# SensWear_Touch.net
KiCad netlist of a schematic drawn in Altium Designer
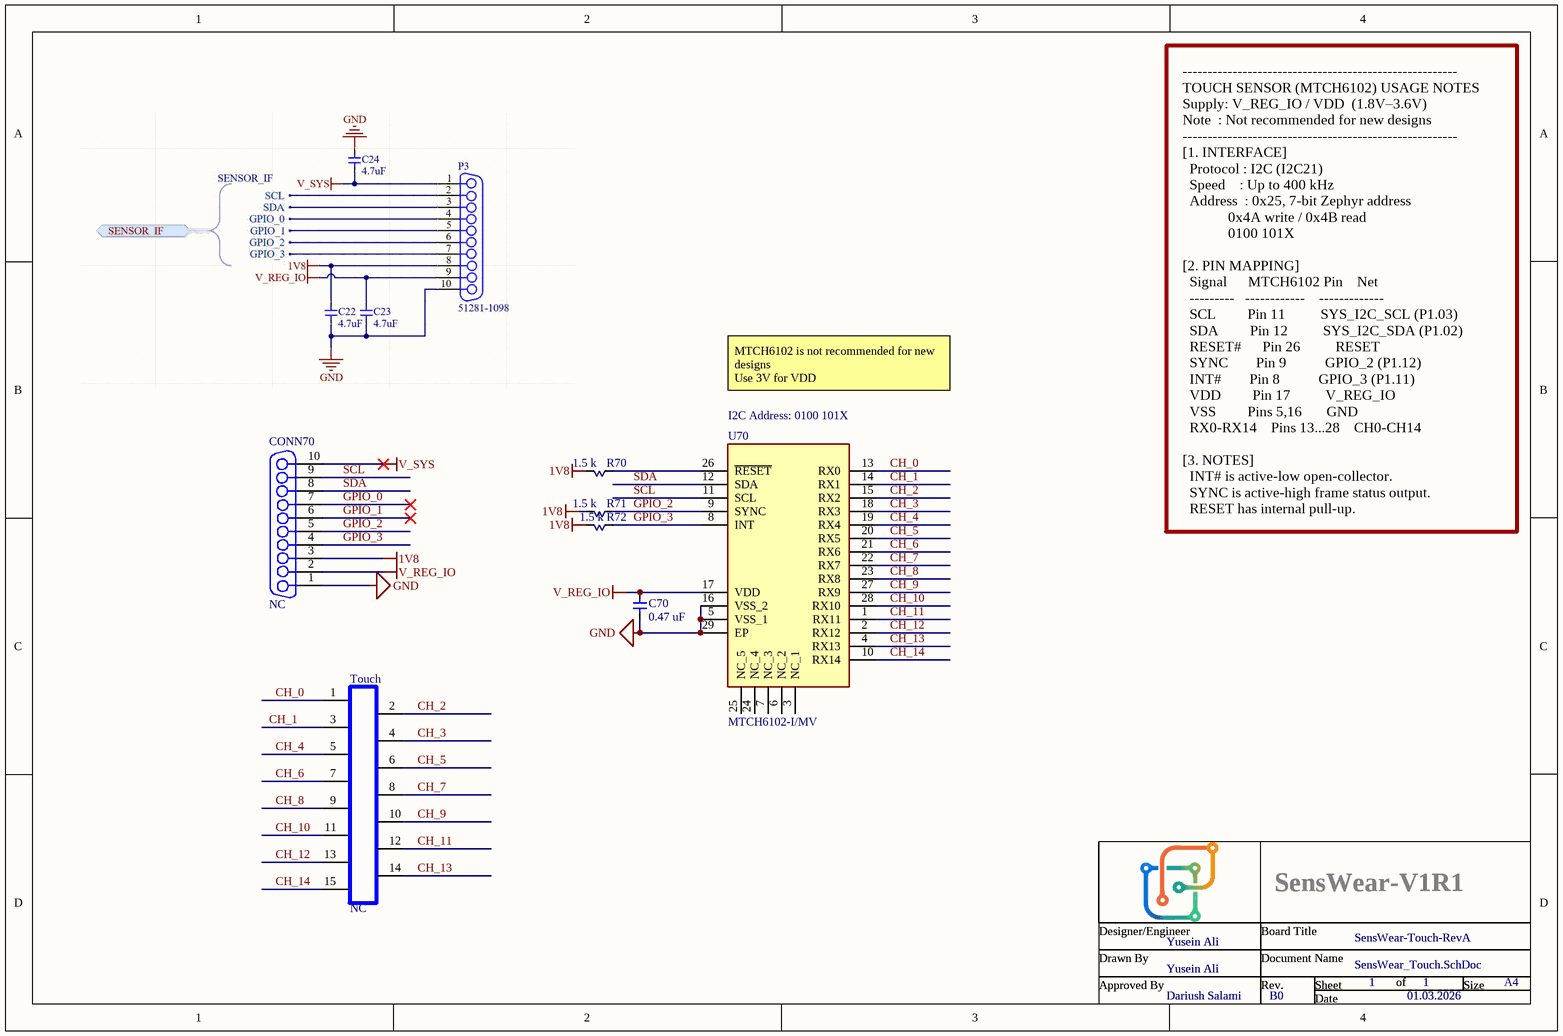
[diagram p0: SensWear_Touch.SchDoc]

(export (version "E")
  (design (tool "Eeschema 10.0.6"))
  (components
    (comp (ref "C70")
      (value "0.47 uF")
      (footprint "CAPC1005X05N")
      (description "CAP CER 0.47UF 10V X5R 0402")
      (fields
        (field (name "MANUFACTURER") "Murata Electronics North America")
        (field (name "MANUFACTURER PART NUMBER") "GRM155R61A474KE15D")
      )
      (libsource (lib "SensWearComponents") (part "GRM155R61A474KE15D"))
    )
    (comp (ref "CONN70")
      (value "NC")
      (footprint "51281-1098-PCB")
      (libsource (lib "SensWearComponents") (part "51281-1098-PCB__2"))
    )
    (comp (ref "R70")
      (value "1.5 k")
      (footprint "RESC1005X04N")
      (description "RES SMD 1.5K OHM 1% 1/10W 0402")
      (fields
        (field (name "MANUFACTURER") "Panasonic Electronic Components")
        (field (name "MANUFACTURER PART NUMBER") "ERJ-2RKF1501X")
      )
      (libsource (lib "SensWearComponents") (part "ERJ-2RKF1501X"))
    )
    (comp (ref "R71")
      (value "1.5 k")
      (footprint "RESC1005X04N")
      (description "RES SMD 1.5K OHM 1% 1/10W 0402")
      (fields
        (field (name "MANUFACTURER") "Panasonic Electronic Components")
        (field (name "MANUFACTURER PART NUMBER") "ERJ-2RKF1501X")
      )
      (libsource (lib "SensWearComponents") (part "ERJ-2RKF1501X"))
    )
    (comp (ref "R72")
      (value "1.5 k")
      (footprint "RESC1005X04N")
      (description "RES SMD 1.5K OHM 1% 1/10W 0402")
      (fields
        (field (name "MANUFACTURER") "Panasonic Electronic Components")
        (field (name "MANUFACTURER PART NUMBER") "ERJ-2RKF1501X")
      )
      (libsource (lib "SensWearComponents") (part "ERJ-2RKF1501X"))
    )
    (comp (ref "Touch")
      (value "NC")
      (footprint "Touch-15Ch-Linear")
      (libsource (lib "SensWearComponents") (part "Touch-15Ch-Linear"))
    )
    (comp (ref "U70")
      (value "MTCH6102-I/MV")
      (footprint "QFN40P400X400X55_HS-29N")
      (description "Capacitive Touch Screen Automotive 28-Pin UQFN EP Tube")
      (fields (field (name "MANUFACTURER") "Microchip") (field (name "CHECKED") "FALSE"))
      (libsource (lib "SensWearComponents") (part "MTCH6102-I/MV"))
    )
  )
  (nets
    (net (code "1") (name "/CH_0") (class "Default")
      (node (ref "Touch") (pin "1") (pinfunction "1_1") (pintype "passive"))
      (node (ref "U70") (pin "13") (pinfunction "RX0_13") (pintype "passive"))
    )
    (net (code "2") (name "/CH_1") (class "Default")
      (node (ref "Touch") (pin "3") (pinfunction "3_3") (pintype "passive"))
      (node (ref "U70") (pin "14") (pinfunction "RX1_14") (pintype "passive"))
    )
    (net (code "3") (name "/CH_2") (class "Default")
      (node (ref "Touch") (pin "2") (pinfunction "2_2") (pintype "passive"))
      (node (ref "U70") (pin "15") (pinfunction "RX2_15") (pintype "passive"))
    )
    (net (code "4") (name "/CH_3") (class "Default")
      (node (ref "Touch") (pin "4") (pinfunction "4_4") (pintype "passive"))
      (node (ref "U70") (pin "18") (pinfunction "RX3_18") (pintype "passive"))
    )
    (net (code "5") (name "/CH_4") (class "Default")
      (node (ref "Touch") (pin "5") (pinfunction "5_5") (pintype "passive"))
      (node (ref "U70") (pin "19") (pinfunction "RX4_19") (pintype "passive"))
    )
    (net (code "6") (name "/CH_5") (class "Default")
      (node (ref "Touch") (pin "6") (pinfunction "6_6") (pintype "passive"))
      (node (ref "U70") (pin "20") (pinfunction "RX5_20") (pintype "passive"))
    )
    (net (code "7") (name "/CH_6") (class "Default")
      (node (ref "Touch") (pin "7") (pinfunction "7_7") (pintype "passive"))
      (node (ref "U70") (pin "21") (pinfunction "RX6_21") (pintype "passive"))
    )
    (net (code "8") (name "/CH_7") (class "Default")
      (node (ref "Touch") (pin "8") (pinfunction "8_8") (pintype "passive"))
      (node (ref "U70") (pin "22") (pinfunction "RX7_22") (pintype "passive"))
    )
    (net (code "9") (name "/CH_8") (class "Default")
      (node (ref "Touch") (pin "9") (pinfunction "9_9") (pintype "passive"))
      (node (ref "U70") (pin "23") (pinfunction "RX8_23") (pintype "passive"))
    )
    (net (code "10") (name "/CH_9") (class "Default")
      (node (ref "Touch") (pin "10") (pinfunction "10_10") (pintype "passive"))
      (node (ref "U70") (pin "27") (pinfunction "RX9_27") (pintype "passive"))
    )
    (net (code "11") (name "/CH_10") (class "Default")
      (node (ref "Touch") (pin "11") (pinfunction "11_11") (pintype "passive"))
      (node (ref "U70") (pin "28") (pinfunction "RX10_28") (pintype "passive"))
    )
    (net (code "12") (name "/CH_11") (class "Default")
      (node (ref "Touch") (pin "12") (pinfunction "12_12") (pintype "passive"))
      (node (ref "U70") (pin "1") (pinfunction "RX11_1") (pintype "passive"))
    )
    (net (code "13") (name "/CH_12") (class "Default")
      (node (ref "Touch") (pin "13") (pinfunction "13_13") (pintype "passive"))
      (node (ref "U70") (pin "2") (pinfunction "RX12_2") (pintype "passive"))
    )
    (net (code "14") (name "/CH_13") (class "Default")
      (node (ref "Touch") (pin "14") (pinfunction "14_14") (pintype "passive"))
      (node (ref "U70") (pin "4") (pinfunction "RX13_4") (pintype "passive"))
    )
    (net (code "15") (name "/CH_14") (class "Default")
      (node (ref "Touch") (pin "15") (pinfunction "15_15") (pintype "passive"))
      (node (ref "U70") (pin "10") (pinfunction "RX14_10") (pintype "passive"))
    )
    (net (code "16") (name "/GPIO_0") (class "Default")
      (node (ref "CONN70") (pin "7") (pinfunction "7_7") (pintype "passive+no_connect"))
    )
    (net (code "17") (name "/GPIO_1") (class "Default")
      (node (ref "CONN70") (pin "6") (pinfunction "6_6") (pintype "passive+no_connect"))
    )
    (net (code "18") (name "/GPIO_2") (class "Default")
      (node (ref "CONN70") (pin "5") (pinfunction "5_5") (pintype "passive"))
      (node (ref "R71") (pin "1") (pinfunction "1_1") (pintype "passive"))
      (node (ref "U70") (pin "9") (pinfunction "SYNC_9") (pintype "passive"))
    )
    (net (code "19") (name "/GPIO_3") (class "Default")
      (node (ref "CONN70") (pin "4") (pinfunction "4_4") (pintype "passive"))
      (node (ref "R72") (pin "1") (pinfunction "1_1") (pintype "passive"))
      (node (ref "U70") (pin "8") (pinfunction "INT_8") (pintype "passive"))
    )
    (net (code "20") (name "/SCL") (class "Default")
      (node (ref "CONN70") (pin "9") (pinfunction "9_9") (pintype "passive"))
      (node (ref "U70") (pin "11") (pinfunction "SCL_11") (pintype "passive"))
    )
    (net (code "21") (name "/SDA") (class "Default")
      (node (ref "CONN70") (pin "8") (pinfunction "8_8") (pintype "passive"))
      (node (ref "U70") (pin "12") (pinfunction "SDA_12") (pintype "passive"))
    )
    (net (code "22") (name "1V8") (class "Default")
      (node (ref "CONN70") (pin "3") (pinfunction "3_3") (pintype "passive"))
      (node (ref "R70") (pin "2") (pinfunction "2_2") (pintype "passive"))
      (node (ref "R71") (pin "2") (pinfunction "2_2") (pintype "passive"))
      (node (ref "R72") (pin "2") (pinfunction "2_2") (pintype "passive"))
    )
    (net (code "23") (name "GND") (class "Default")
      (node (ref "C70") (pin "2") (pinfunction "2_2") (pintype "passive"))
      (node (ref "CONN70") (pin "1") (pinfunction "1_1") (pintype "passive"))
      (node (ref "U70") (pin "16") (pinfunction "VSS_2_16") (pintype "passive"))
      (node (ref "U70") (pin "29") (pinfunction "EP_29") (pintype "passive"))
      (node (ref "U70") (pin "5") (pinfunction "VSS_1_5") (pintype "passive"))
    )
    (net (code "24") (name "Net-(U70-~{RESET})") (class "Default")
      (node (ref "R70") (pin "1") (pinfunction "1_1") (pintype "passive"))
      (node (ref "U70") (pin "26") (pinfunction "~{RESET}_26") (pintype "passive"))
    )
    (net (code "25") (name "V_REG_IO") (class "Default")
      (node (ref "C70") (pin "1") (pinfunction "1_1") (pintype "passive"))
      (node (ref "CONN70") (pin "2") (pinfunction "2_2") (pintype "passive"))
      (node (ref "U70") (pin "17") (pinfunction "VDD_17") (pintype "passive"))
    )
    (net (code "26") (name "V_SYS") (class "Default")
      (node (ref "CONN70") (pin "10") (pinfunction "10_10") (pintype "passive"))
    )
    (net (code "27") (name "unconnected-(U70-NC_1-Pad3)") (class "Default")
      (node (ref "U70") (pin "3") (pinfunction "NC_1_3") (pintype "passive"))
    )
    (net (code "28") (name "unconnected-(U70-NC_2-Pad6)") (class "Default")
      (node (ref "U70") (pin "6") (pinfunction "NC_2_6") (pintype "passive"))
    )
    (net (code "29") (name "unconnected-(U70-NC_3-Pad7)") (class "Default")
      (node (ref "U70") (pin "7") (pinfunction "NC_3_7") (pintype "passive"))
    )
    (net (code "30") (name "unconnected-(U70-NC_4-Pad24)") (class "Default")
      (node (ref "U70") (pin "24") (pinfunction "NC_4_24") (pintype "passive"))
    )
    (net (code "31") (name "unconnected-(U70-NC_5-Pad25)") (class "Default")
      (node (ref "U70") (pin "25") (pinfunction "NC_5_25") (pintype "passive"))
    )
  )
)
